# MDL-485.net
KiCad netlist of a schematic drawn in Altium Designer
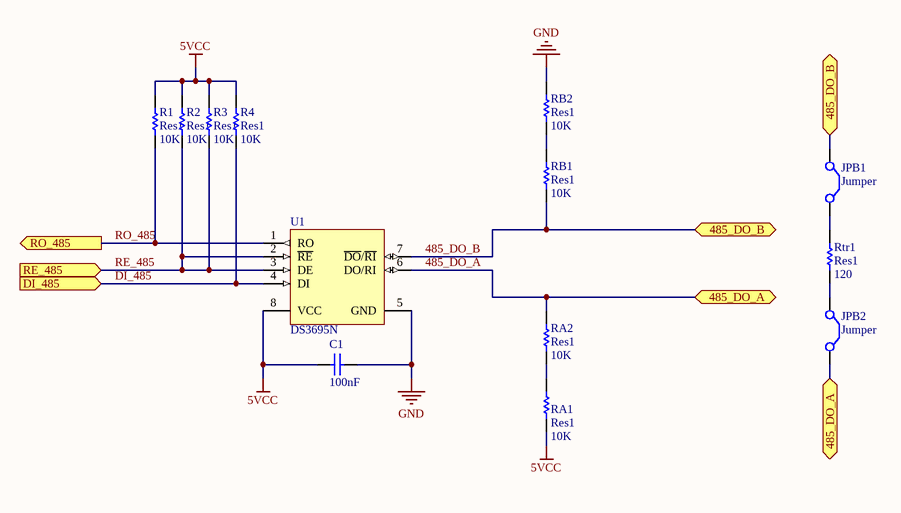
[diagram p0: MDL-485.SchDoc]

(export (version "E")
  (design (tool "Eeschema 10.0.6"))
  (components
    (comp (ref "C1")
      (value "100nF")
      (footprint "VP44-2.5")
      (description "Dipped Radial Multilayer Ceramic Capacitor X7R: 220nF, 100V")
      (fields (field (name "Comment") "VP44BY224JB") (field (name "PUBLISHER") "Altium Limited"))
      (libsource (lib "Vishay Vitramon Ceramic Dipped Capacitor") (part "VP44BY224JB"))
    )
    (comp (ref "JPB1")
      (value "Jumper")
      (footprint "RAD-0.2")
      (description "Jumper Wire")
      (fields (field (name "PUBLISHER") "Altium Limited"))
      (libsource (lib "Miscellaneous Devices") (part "Jumper"))
    )
    (comp (ref "JPB2")
      (value "Jumper")
      (footprint "RAD-0.2")
      (description "Jumper Wire")
      (fields (field (name "PUBLISHER") "Altium Limited"))
      (libsource (lib "Miscellaneous Devices") (part "Jumper"))
    )
    (comp (ref "R1")
      (value "Res1")
      (footprint "AXIAL-0.3")
      (description "Resistor")
      (fields (field (name "ALTIUM_VALUE") "10K") (field (name "PUBLISHER") "Altium Limited"))
      (libsource (lib "Miscellaneous Devices") (part "Res1"))
    )
    (comp (ref "R2")
      (value "Res1")
      (footprint "AXIAL-0.3")
      (description "Resistor")
      (fields (field (name "ALTIUM_VALUE") "10K") (field (name "PUBLISHER") "Altium Limited"))
      (libsource (lib "Miscellaneous Devices") (part "Res1"))
    )
    (comp (ref "R3")
      (value "Res1")
      (footprint "AXIAL-0.3")
      (description "Resistor")
      (fields (field (name "ALTIUM_VALUE") "10K") (field (name "PUBLISHER") "Altium Limited"))
      (libsource (lib "Miscellaneous Devices") (part "Res1"))
    )
    (comp (ref "R4")
      (value "Res1")
      (footprint "AXIAL-0.3")
      (description "Resistor")
      (fields (field (name "ALTIUM_VALUE") "10K") (field (name "PUBLISHER") "Altium Limited"))
      (libsource (lib "Miscellaneous Devices") (part "Res1"))
    )
    (comp (ref "RA1")
      (value "Res1")
      (footprint "AXIAL-0.3")
      (description "Resistor")
      (fields (field (name "ALTIUM_VALUE") "10K") (field (name "PUBLISHER") "Altium Limited"))
      (libsource (lib "Miscellaneous Devices") (part "Res1"))
    )
    (comp (ref "RA2")
      (value "Res1")
      (footprint "AXIAL-0.3")
      (description "Resistor")
      (fields (field (name "ALTIUM_VALUE") "10K") (field (name "PUBLISHER") "Altium Limited"))
      (libsource (lib "Miscellaneous Devices") (part "Res1"))
    )
    (comp (ref "RB1")
      (value "Res1")
      (footprint "AXIAL-0.3")
      (description "Resistor")
      (fields (field (name "ALTIUM_VALUE") "10K") (field (name "PUBLISHER") "Altium Limited"))
      (libsource (lib "Miscellaneous Devices") (part "Res1"))
    )
    (comp (ref "RB2")
      (value "Res1")
      (footprint "AXIAL-0.3")
      (description "Resistor")
      (fields (field (name "ALTIUM_VALUE") "10K") (field (name "PUBLISHER") "Altium Limited"))
      (libsource (lib "Miscellaneous Devices") (part "Res1"))
    )
    (comp (ref "Rtr1")
      (value "Res1")
      (footprint "AXIAL-0.3")
      (description "Resistor")
      (fields (field (name "ALTIUM_VALUE") "120") (field (name "PUBLISHER") "Altium Limited"))
      (libsource (lib "Miscellaneous Devices") (part "Res1"))
    )
    (comp (ref "U1")
      (value "DS3695N")
      (footprint "N08E")
      (description "Multipoint RS485/RS422 Transceiver/Repeater")
      (fields
        (field (name "MANUFACTURER") "National Semiconductor")
        (field (name "DIGIKEYPARTNUMBER") "DS3695N-ND")
        (field (name "PUBLISHER") "Altium Limited")
      )
      (libsource (lib "NSC Interface") (part "DS3695N"))
    )
  )
  (nets
    (net (code "1") (name "/485_DO_A") (class "Default")
      (node (ref "JPB2") (pin "2") (pinfunction "C2_2") (pintype "passive"))
      (node (ref "RA2") (pin "2") (pinfunction "2_2") (pintype "passive"))
      (node (ref "U1") (pin "6") (pinfunction "DO/RI_6") (pintype "bidirectional"))
    )
    (net (code "2") (name "/485_DO_B") (class "Default")
      (node (ref "JPB1") (pin "1") (pinfunction "C1_1") (pintype "passive"))
      (node (ref "RB1") (pin "1") (pinfunction "1_1") (pintype "passive"))
      (node (ref "U1") (pin "7") (pinfunction "~{DO}/~{RI}_7") (pintype "bidirectional"))
    )
    (net (code "3") (name "/DI_485") (class "Default")
      (node (ref "R4") (pin "1") (pinfunction "1_1") (pintype "passive"))
      (node (ref "U1") (pin "4") (pinfunction "DI_4") (pintype "input"))
    )
    (net (code "4") (name "/RE_485") (class "Default")
      (node (ref "R2") (pin "1") (pinfunction "1_1") (pintype "passive"))
      (node (ref "R3") (pin "1") (pinfunction "1_1") (pintype "passive"))
      (node (ref "U1") (pin "2") (pinfunction "~{RE}_2") (pintype "input"))
      (node (ref "U1") (pin "3") (pinfunction "DE_3") (pintype "input"))
    )
    (net (code "5") (name "/RO_485") (class "Default")
      (node (ref "R1") (pin "1") (pinfunction "1_1") (pintype "passive"))
      (node (ref "U1") (pin "1") (pinfunction "RO_1") (pintype "output"))
    )
    (net (code "6") (name "5VCC") (class "Default")
      (node (ref "C1") (pin "1") (pinfunction "1_1") (pintype "passive"))
      (node (ref "R1") (pin "2") (pinfunction "2_2") (pintype "passive"))
      (node (ref "R2") (pin "2") (pinfunction "2_2") (pintype "passive"))
      (node (ref "R3") (pin "2") (pinfunction "2_2") (pintype "passive"))
      (node (ref "R4") (pin "2") (pinfunction "2_2") (pintype "passive"))
      (node (ref "RA1") (pin "1") (pinfunction "1_1") (pintype "passive"))
      (node (ref "U1") (pin "8") (pinfunction "VCC_8") (pintype "power_in"))
    )
    (net (code "7") (name "GND") (class "Default")
      (node (ref "C1") (pin "2") (pinfunction "2_2") (pintype "passive"))
      (node (ref "RB2") (pin "2") (pinfunction "2_2") (pintype "passive"))
      (node (ref "U1") (pin "5") (pinfunction "GND_5") (pintype "power_in"))
    )
    (net (code "8") (name "Net-(JPB1-C2)") (class "Default")
      (node (ref "JPB1") (pin "2") (pinfunction "C2_2") (pintype "passive"))
      (node (ref "Rtr1") (pin "2") (pinfunction "2_2") (pintype "passive"))
    )
    (net (code "9") (name "Net-(JPB2-C1)") (class "Default")
      (node (ref "JPB2") (pin "1") (pinfunction "C1_1") (pintype "passive"))
      (node (ref "Rtr1") (pin "1") (pinfunction "1_1") (pintype "passive"))
    )
    (net (code "10") (name "Net-(RA1-Pad2)") (class "Default")
      (node (ref "RA1") (pin "2") (pinfunction "2_2") (pintype "passive"))
      (node (ref "RA2") (pin "1") (pinfunction "1_1") (pintype "passive"))
    )
    (net (code "11") (name "Net-(RB1-Pad2)") (class "Default")
      (node (ref "RB1") (pin "2") (pinfunction "2_2") (pintype "passive"))
      (node (ref "RB2") (pin "1") (pinfunction "1_1") (pintype "passive"))
    )
  )
)
